# ReuseBlock_MSDriver2_0_2025-01-31.net
KiCad netlist of a schematic drawn in EasyEDA Pro
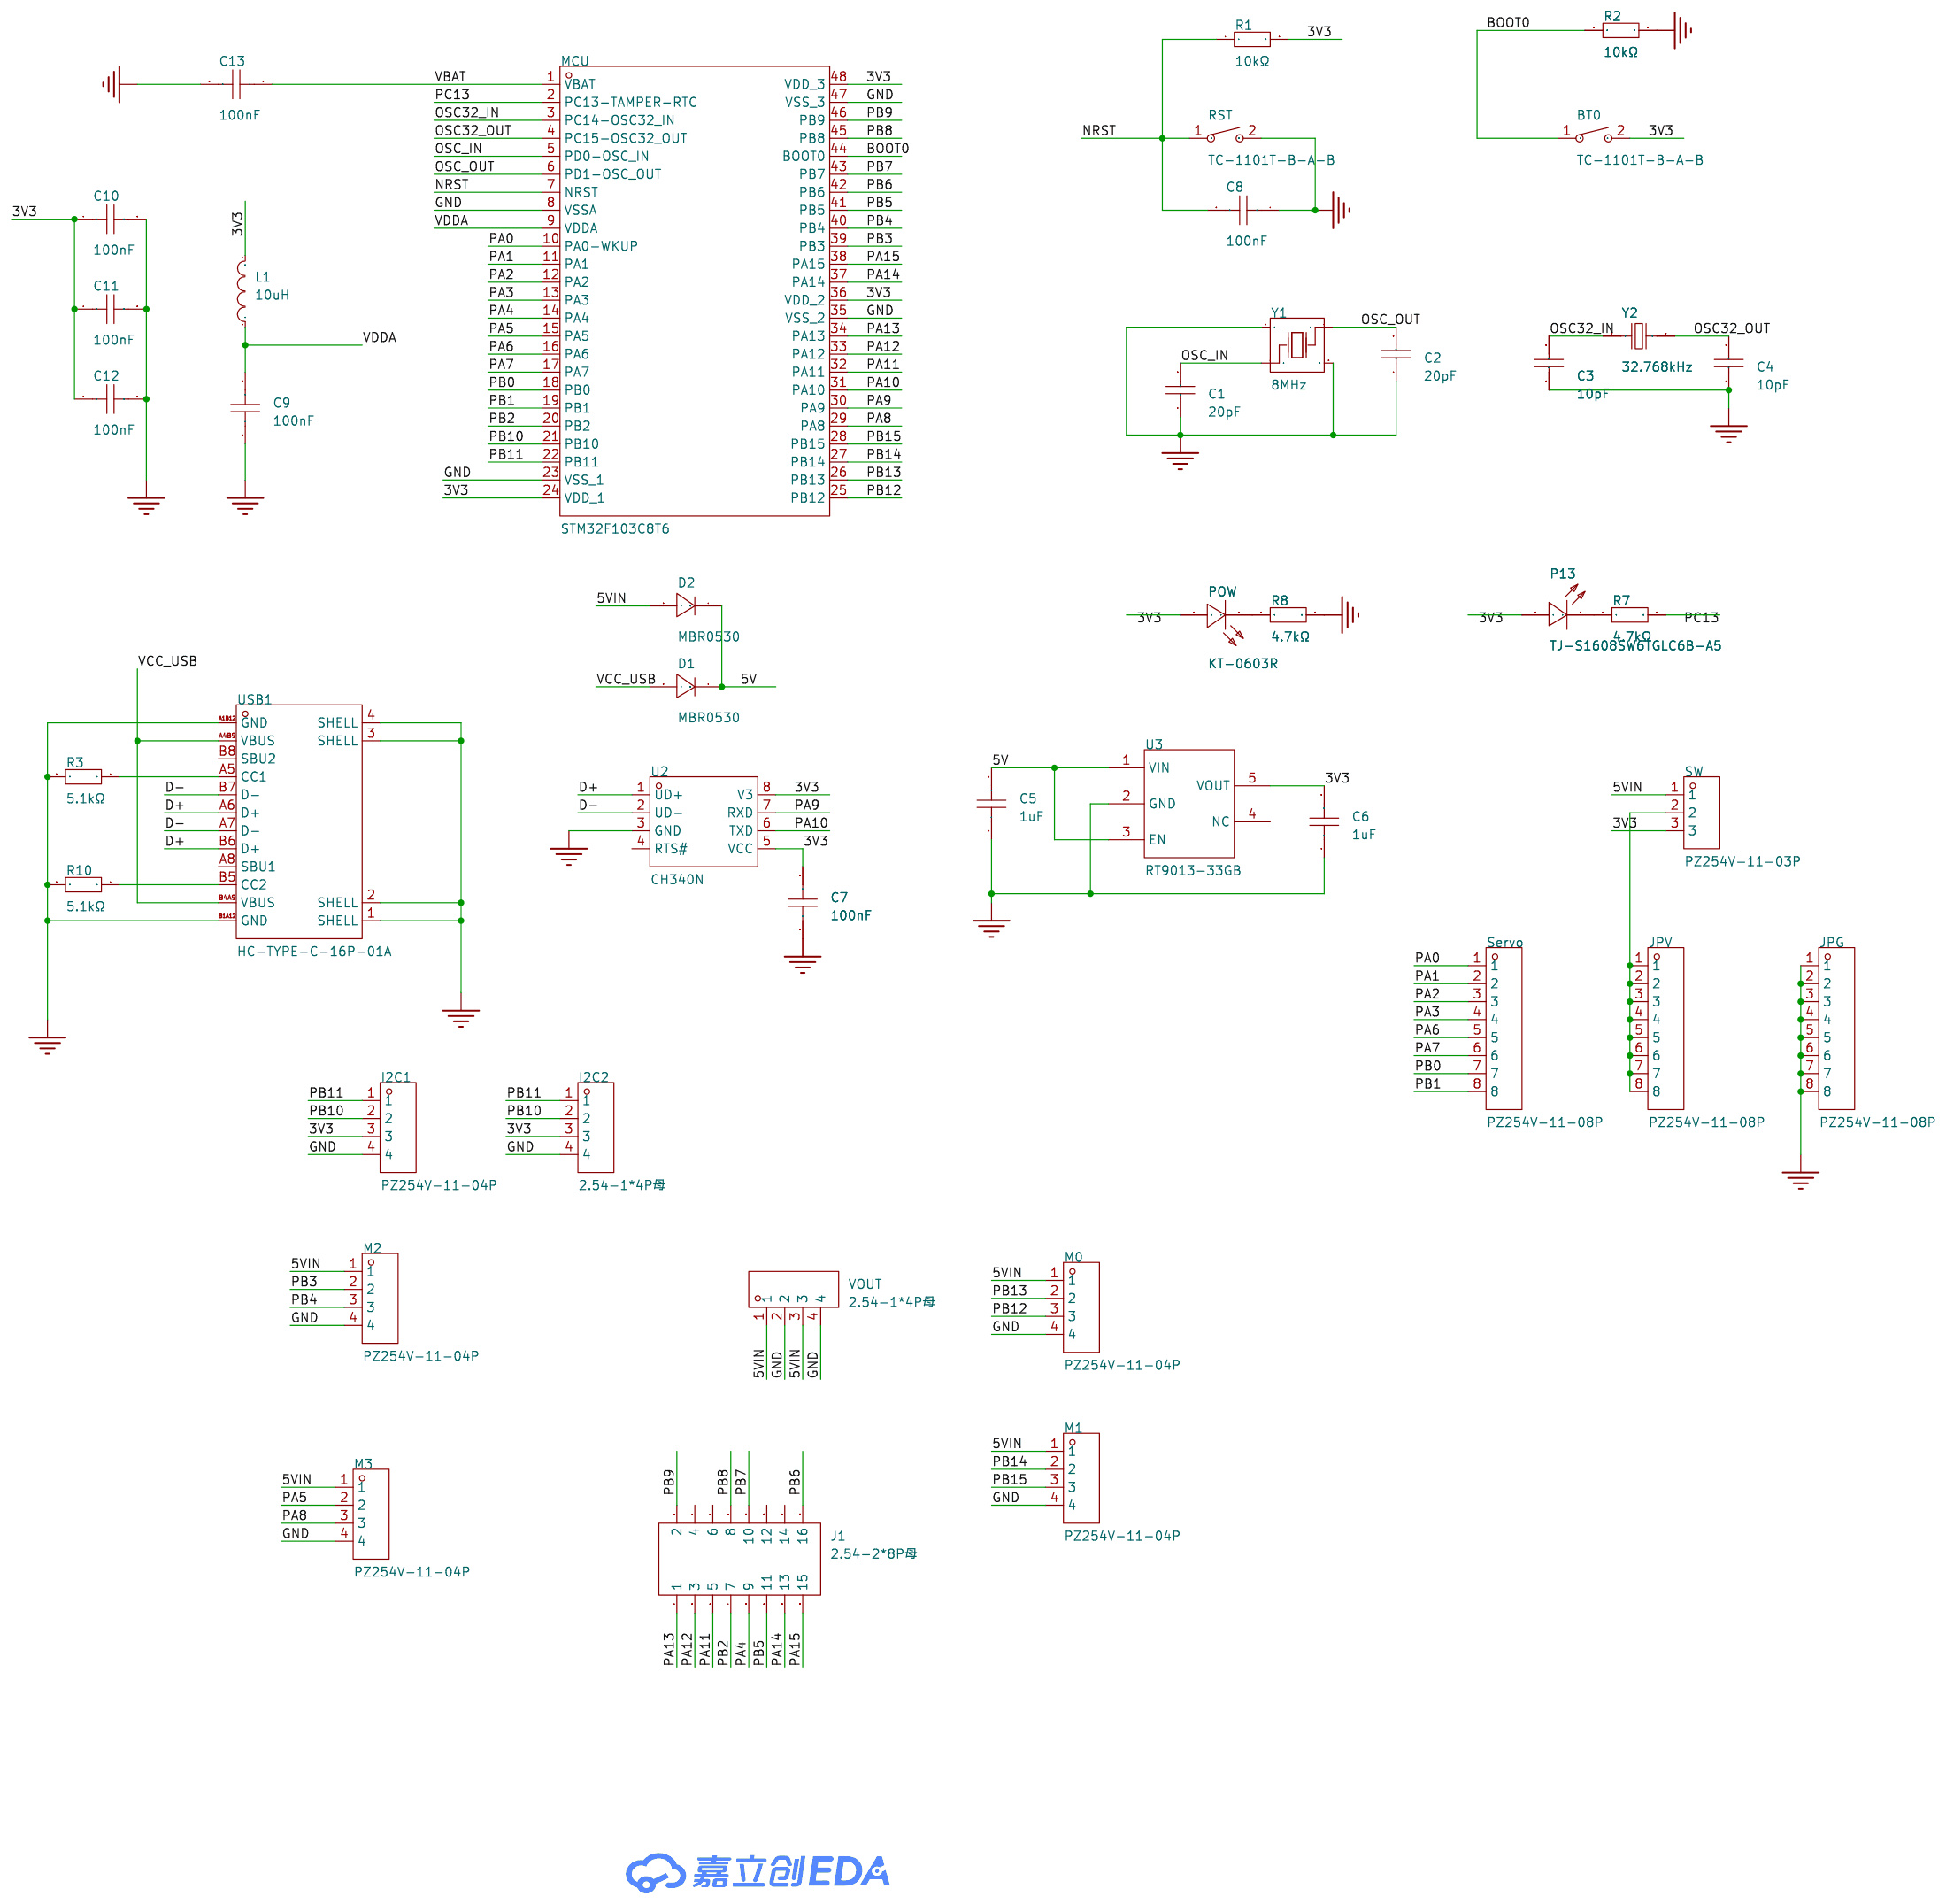
[diagram p0: schematic sheet]

(export (version "E")
  (design (tool "Eeschema 10.0.6"))
  (components
    (comp (ref "BT0")
      (value "TC-1101T-B-A-B")
      (footprint "easyedapro:KEY-TH_2P-L6.0-W3.5-P6.50")
      (fields (field (name "Manufacturer") "XKB Connectivity(中国星坤)"))
      (libsource (lib "easyedapro") (part "TC-1101T-B-A-B"))
    )
    (comp (ref "C1")
      (value "20pF")
      (footprint "easyedapro:C0603")
      (description "容值:20pF;精度:±5%;额定电压:50V;材质(温度系数):C0G;")
      (fields
        (field (name "Manufacturer Part") "CL10C200JB8NNNC")
        (field (name "Manufacturer") "SAMSUNG(三星)")
      )
      (libsource (lib "easyedapro") (part "CL10C200JB8NNNC"))
    )
    (comp (ref "C2")
      (value "20pF")
      (footprint "easyedapro:C0603")
      (description "容值:20pF;精度:±5%;额定电压:50V;材质(温度系数):C0G;")
      (fields
        (field (name "Manufacturer Part") "CL10C200JB8NNNC")
        (field (name "Manufacturer") "SAMSUNG(三星)")
      )
      (libsource (lib "easyedapro") (part "CL10C200JB8NNNC"))
    )
    (comp (ref "C3")
      (value "10pF")
      (footprint "easyedapro:C0603")
      (description "容值:10pF;精度:±5%;额定电压:50V;材质(温度系数):C0G;")
      (fields
        (field (name "Manufacturer Part") "CL10C100JB8NNNC")
        (field (name "Manufacturer") "SAMSUNG(三星)")
      )
      (libsource (lib "easyedapro") (part "CL10C100JB8NNNC"))
    )
    (comp (ref "C4")
      (value "10pF")
      (footprint "easyedapro:C0603")
      (description "容值:10pF;精度:±5%;额定电压:50V;材质(温度系数):C0G;")
      (fields
        (field (name "Manufacturer Part") "CL10C100JB8NNNC")
        (field (name "Manufacturer") "SAMSUNG(三星)")
      )
      (libsource (lib "easyedapro") (part "CL10C100JB8NNNC"))
    )
    (comp (ref "C5")
      (value "1uF")
      (footprint "easyedapro:C0603")
      (description "容值:1uF;精度:±10%;额定电压:50V;材质(温度系数):X5R;")
      (fields
        (field (name "Manufacturer Part") "CL10A105KB8NNNC")
        (field (name "Manufacturer") "SAMSUNG(三星)")
      )
      (libsource (lib "easyedapro") (part "CL10A105KB8NNNC"))
    )
    (comp (ref "C6")
      (value "1uF")
      (footprint "easyedapro:C0603")
      (description "容值:1uF;精度:±10%;额定电压:50V;材质(温度系数):X5R;")
      (fields
        (field (name "Manufacturer Part") "CL10A105KB8NNNC")
        (field (name "Manufacturer") "SAMSUNG(三星)")
      )
      (libsource (lib "easyedapro") (part "CL10A105KB8NNNC"))
    )
    (comp (ref "C7")
      (value "100nF")
      (footprint "easyedapro:C0603")
      (description "容值:100nF;精度:±10%;额定电压:50V;材质(温度系数):X7R;")
      (fields
        (field (name "Manufacturer Part") "CGA0603X7R104K500JT")
        (field (name "Manufacturer") "HRE(芯声)")
      )
      (libsource (lib "easyedapro") (part "CGA0603X7R104K500JT"))
    )
    (comp (ref "C8")
      (value "100nF")
      (footprint "easyedapro:C0603")
      (description "容值:100nF;精度:±10%;额定电压:50V;材质(温度系数):X7R;")
      (fields
        (field (name "Manufacturer Part") "CGA0603X7R104K500JT")
        (field (name "Manufacturer") "HRE(芯声)")
      )
      (libsource (lib "easyedapro") (part "CGA0603X7R104K500JT"))
    )
    (comp (ref "C9")
      (value "100nF")
      (footprint "easyedapro:C0603")
      (description "容值:100nF;精度:±10%;额定电压:50V;材质(温度系数):X7R;")
      (fields
        (field (name "Manufacturer Part") "CGA0603X7R104K500JT")
        (field (name "Manufacturer") "HRE(芯声)")
      )
      (libsource (lib "easyedapro") (part "CGA0603X7R104K500JT"))
    )
    (comp (ref "C10")
      (value "100nF")
      (footprint "easyedapro:C0603")
      (description "容值:100nF;精度:±10%;额定电压:50V;材质(温度系数):X7R;")
      (fields
        (field (name "Manufacturer Part") "CGA0603X7R104K500JT")
        (field (name "Manufacturer") "HRE(芯声)")
      )
      (libsource (lib "easyedapro") (part "CGA0603X7R104K500JT"))
    )
    (comp (ref "C11")
      (value "100nF")
      (footprint "easyedapro:C0603")
      (description "容值:100nF;精度:±10%;额定电压:50V;材质(温度系数):X7R;")
      (fields
        (field (name "Manufacturer Part") "CGA0603X7R104K500JT")
        (field (name "Manufacturer") "HRE(芯声)")
      )
      (libsource (lib "easyedapro") (part "CGA0603X7R104K500JT"))
    )
    (comp (ref "C12")
      (value "100nF")
      (footprint "easyedapro:C0603")
      (description "容值:100nF;精度:±10%;额定电压:50V;材质(温度系数):X7R;")
      (fields
        (field (name "Manufacturer Part") "CGA0603X7R104K500JT")
        (field (name "Manufacturer") "HRE(芯声)")
      )
      (libsource (lib "easyedapro") (part "CGA0603X7R104K500JT"))
    )
    (comp (ref "C13")
      (value "100nF")
      (footprint "easyedapro:C0603")
      (description "容值:100nF;精度:±10%;额定电压:50V;材质(温度系数):X7R;")
      (fields
        (field (name "Manufacturer Part") "CGA0603X7R104K500JT")
        (field (name "Manufacturer") "HRE(芯声)")
      )
      (libsource (lib "easyedapro") (part "CGA0603X7R104K500JT"))
    )
    (comp (ref "D1")
      (value "MBR0530")
      (footprint "easyedapro:SOD-123_L2.8-W1.8-LS3.7-RD")
      (description "二极管配置:-;正向压降(Vf):550mV@500mA;直流反向耐压(Vr):30V;整流电流:500mA;")
      (fields (field (name "Manufacturer") "CJ(江苏长电/长晶)"))
      (libsource (lib "easyedapro") (part "MBR0530"))
    )
    (comp (ref "D2")
      (value "MBR0530")
      (footprint "easyedapro:SOD-123_L2.8-W1.8-LS3.7-RD")
      (description "二极管配置:-;正向压降(Vf):550mV@500mA;直流反向耐压(Vr):30V;整流电流:500mA;")
      (fields (field (name "Manufacturer") "CJ(江苏长电/长晶)"))
      (libsource (lib "easyedapro") (part "MBR0530"))
    )
    (comp (ref "I2C1")
      (value "PZ254V-11-04P")
      (footprint "easyedapro:HDR-TH_4P-P2.54-V-M")
      (fields (field (name "Manufacturer") "XFCN(兴飞)"))
      (libsource (lib "easyedapro") (part "PZ254V-11-04P_C2691448"))
    )
    (comp (ref "I2C2")
      (value "2.54-1*4P母")
      (footprint "easyedapro:HDR-TH_4P-P2.54-V-F")
      (fields (field (name "Manufacturer") "BOOMELE(博穆精密)"))
      (libsource (lib "easyedapro") (part "2.54-1*4P母"))
    )
    (comp (ref "J1")
      (value "2.54-2*8P母")
      (footprint "easyedapro:HDR-TH_16P-P2.54-V-F-R2-C8-S2.54")
      (description "插孔结构:2x8P;间距:2.54mm;行距:2.54mm;安装类型:直插;排数:双排;总孔位数:16P;塑高:-;触头材质:黄铜;触头镀层:-;")
      (fields (field (name "Manufacturer") "BOOMELE(博穆精密)"))
      (libsource (lib "easyedapro") (part "Header-Female-2.54_2x8"))
    )
    (comp (ref "JPG")
      (value "PZ254V-11-08P")
      (footprint "easyedapro:HDR-TH_8P-P2.54-V-M")
      (fields (field (name "Manufacturer") "XFCN(兴飞)"))
      (libsource (lib "easyedapro") (part "PZ254V-11-08P"))
    )
    (comp (ref "JPV")
      (value "PZ254V-11-08P")
      (footprint "easyedapro:HDR-TH_8P-P2.54-V-M")
      (fields (field (name "Manufacturer") "XFCN(兴飞)"))
      (libsource (lib "easyedapro") (part "PZ254V-11-08P"))
    )
    (comp (ref "L1")
      (value "10uH")
      (footprint "easyedapro:L0805")
      (description "电感值:10uH;精度:±10%;额定电流:15mA;饱和电流(Isat):-;直流电阻(DCR):1.15Ω;")
      (fields
        (field (name "Manufacturer Part") "SDFL2012S100KTF")
        (field (name "Manufacturer") "Sunlord(顺络)")
      )
      (libsource (lib "easyedapro") (part "SDFL2012S100KTF"))
    )
    (comp (ref "M0")
      (value "PZ254V-11-04P")
      (footprint "easyedapro:HDR-TH_4P-P2.54-V-M")
      (fields (field (name "Manufacturer") "XFCN(兴飞)"))
      (libsource (lib "easyedapro") (part "PZ254V-11-04P_C2691448"))
    )
    (comp (ref "M1")
      (value "PZ254V-11-04P")
      (footprint "easyedapro:HDR-TH_4P-P2.54-V-M")
      (fields (field (name "Manufacturer") "XFCN(兴飞)"))
      (libsource (lib "easyedapro") (part "PZ254V-11-04P_C2691448"))
    )
    (comp (ref "M2")
      (value "PZ254V-11-04P")
      (footprint "easyedapro:HDR-TH_4P-P2.54-V-M")
      (fields (field (name "Manufacturer") "XFCN(兴飞)"))
      (libsource (lib "easyedapro") (part "PZ254V-11-04P_C2691448"))
    )
    (comp (ref "M3")
      (value "PZ254V-11-04P")
      (footprint "easyedapro:HDR-TH_4P-P2.54-V-M")
      (fields (field (name "Manufacturer") "XFCN(兴飞)"))
      (libsource (lib "easyedapro") (part "PZ254V-11-04P_C2691448"))
    )
    (comp (ref "MCU")
      (value "STM32F103C8T6")
      (footprint "easyedapro:LQFP-48_L7.0-W7.0-P0.50-LS9.0-BL")
      (description "CPU内核:ARM-M3;CPU最大主频:72MHz;应用领域:-;")
      (fields (field (name "Manufacturer") "ST(意法半导体)"))
      (libsource (lib "easyedapro") (part "STM32F103C8T6"))
    )
    (comp (ref "P13")
      (value "TJ-S1608SW6TGLC6B-A5")
      (footprint "easyedapro:LED0603-R-RD_BLUE")
      (description "发光颜色:蓝色;功率:111mW;正向电流:20mA;主波长:460nm;二极管配置:-;透镜颜色:无色透明透镜;色温:-;发光角度:120°;载带方式:-;工作温度:-40°C~+80°C;")
      (fields (field (name "Manufacturer") "TOGIALED(统佳)"))
      (libsource (lib "easyedapro") (part "TJ-S1608SW6TGLC6B-A5"))
    )
    (comp (ref "POW")
      (value "KT-0603R")
      (footprint "easyedapro:LED0603-RD")
      (description "发光颜色:红色;功率:-;正向电流:-;主波长:-;二极管配置:-;透镜颜色:-;色温:-;发光角度:-;载带方式:-;工作温度:-40°C~+85°C;")
      (fields (field (name "Manufacturer") "KENTO"))
      (libsource (lib "easyedapro") (part "KT-0603R"))
    )
    (comp (ref "R1")
      (value "10kΩ")
      (fields
        (field (name "Manufacturer Part") "0603WAF1002T5E")
        (field (name "Manufacturer") "UNI-ROYAL(厚声)")
      )
      (libsource (lib "easyedapro") (part "电阻"))
    )
    (comp (ref "R2")
      (value "10kΩ")
      (fields
        (field (name "Manufacturer Part") "0603WAF1002T5E")
        (field (name "Manufacturer") "UNI-ROYAL(厚声)")
      )
      (libsource (lib "easyedapro") (part "电阻"))
    )
    (comp (ref "R3")
      (value "5.1kΩ")
      (fields
        (field (name "Manufacturer Part") "0603WAF5101T5E")
        (field (name "Manufacturer") "UNI-ROYAL(厚声)")
      )
      (libsource (lib "easyedapro") (part "电阻"))
    )
    (comp (ref "R7")
      (value "4.7kΩ")
      (fields
        (field (name "Manufacturer Part") "0603WAF4701T5E")
        (field (name "Manufacturer") "UNI-ROYAL(厚声)")
      )
      (libsource (lib "easyedapro") (part "电阻"))
    )
    (comp (ref "R8")
      (value "4.7kΩ")
      (fields
        (field (name "Manufacturer Part") "0603WAF4701T5E")
        (field (name "Manufacturer") "UNI-ROYAL(厚声)")
      )
      (libsource (lib "easyedapro") (part "电阻"))
    )
    (comp (ref "R10")
      (value "5.1kΩ")
      (fields
        (field (name "Manufacturer Part") "0603WAF5101T5E")
        (field (name "Manufacturer") "UNI-ROYAL(厚声)")
      )
      (libsource (lib "easyedapro") (part "电阻"))
    )
    (comp (ref "RST")
      (value "TC-1101T-B-A-B")
      (footprint "easyedapro:KEY-TH_2P-L6.0-W3.5-P6.50")
      (fields (field (name "Manufacturer") "XKB Connectivity(中国星坤)"))
      (libsource (lib "easyedapro") (part "TC-1101T-B-A-B"))
    )
    (comp (ref "Servo")
      (value "PZ254V-11-08P")
      (footprint "easyedapro:HDR-TH_8P-P2.54-V-M")
      (fields (field (name "Manufacturer") "XFCN(兴飞)"))
      (libsource (lib "easyedapro") (part "PZ254V-11-08P"))
    )
    (comp (ref "SW")
      (value "PZ254V-11-03P")
      (footprint "easyedapro:HDR-TH_3P-P2.54-V-M")
      (fields (field (name "Manufacturer") "XFCN(兴飞)"))
      (libsource (lib "easyedapro") (part "PZ254V-11-03P_C2937625"))
    )
    (comp (ref "U2")
      (value "CH340N")
      (footprint "easyedapro:SOP-8_L4.9-W3.9-P1.27-LS6.0-BL")
      (description "应用功能:USB转串口;接口协议:USB 2.0;通道数:1;数据速率:2Mbps;")
      (fields (field (name "Manufacturer") "WCH(南京沁恒)"))
      (libsource (lib "easyedapro") (part "CH340N_C2977777"))
    )
    (comp (ref "U3")
      (value "RT9013-33GB")
      (footprint "easyedapro:SOT-23-5_L3.0-W1.7-P0.95-LS2.8-BL")
      (description "输出类型:固定;最大输入电压:5.5V;输出电压:3.3V;输出电流:500mA;电源纹波抑制比(PSRR):50dB@(10kHz);输出极性:正极;")
      (fields (field (name "Manufacturer") "RICHTEK(立锜)"))
      (libsource (lib "easyedapro") (part "RT9013-33GB"))
    )
    (comp (ref "USB1")
      (value "HC-TYPE-C-16P-01A")
      (footprint "easyedapro:USB-C-SMD_HC-TYPE-C-16P-01A")
      (fields (field (name "Manufacturer") "HCTL(华灿天禄)"))
      (libsource (lib "easyedapro") (part "HC-TYPE-C-16P-01A"))
    )
    (comp (ref "VOUT")
      (value "2.54-1*4P母")
      (footprint "easyedapro:HDR-TH_4P-P2.54-V-F")
      (fields (field (name "Manufacturer") "BOOMELE(博穆精密)"))
      (libsource (lib "easyedapro") (part "2.54-1*4P母"))
    )
    (comp (ref "Y1")
      (value "8MHz")
      (footprint "easyedapro:CRYSTAL-SMD_4P-L3.2-W2.5-BL")
      (description "晶振类型:贴片晶振;频率:8MHz;常温频差:±10ppm;负载电容:10pF;频率稳定度(全温):±15ppm;")
      (fields (field (name "Manufacturer Part") "TAXM8M4RDBCCT2T") (field (name "Manufacturer") "YJX(雅晶鑫)"))
      (libsource (lib "easyedapro") (part "TAXM8M4RDBCCT2T"))
    )
    (comp (ref "Y2")
      (value "32.768kHz")
      (footprint "easyedapro:FC-135R_L3.2-W1.5")
      (description "晶振类型:贴片晶振;频率:32.768kHz;常温频差:±20ppm;负载电容:12.5pF;")
      (fields (field (name "Manufacturer Part") "Q13FC13500004") (field (name "Manufacturer") "EPSON(爱普生)"))
      (libsource (lib "easyedapro") (part "Q13FC1350000400"))
    )
  )
  (nets
    (net (code "1") (name "/3V3") (class "Default")
      (node (ref "BT0") (pin "2") (pinfunction "2_2") (pintype "unspecified"))
      (node (ref "C10") (pin "1") (pinfunction "1_1") (pintype "unspecified"))
      (node (ref "C11") (pin "1") (pinfunction "1_1") (pintype "unspecified"))
      (node (ref "C12") (pin "1") (pinfunction "1_1") (pintype "unspecified"))
      (node (ref "C6") (pin "2") (pinfunction "2_2") (pintype "unspecified"))
      (node (ref "C7") (pin "2") (pinfunction "2_2") (pintype "unspecified"))
      (node (ref "I2C1") (pin "3") (pinfunction "3_3") (pintype "unspecified"))
      (node (ref "I2C2") (pin "3") (pinfunction "3_3") (pintype "unspecified"))
      (node (ref "L1") (pin "2") (pinfunction "2_2") (pintype "unspecified"))
      (node (ref "MCU") (pin "24") (pinfunction "VDD_1_24") (pintype "unspecified"))
      (node (ref "MCU") (pin "36") (pinfunction "VDD_2_36") (pintype "unspecified"))
      (node (ref "MCU") (pin "48") (pinfunction "VDD_3_48") (pintype "unspecified"))
      (node (ref "P13") (pin "1") (pinfunction "A_1") (pintype "unspecified"))
      (node (ref "POW") (pin "2") (pinfunction "A_2") (pintype "unspecified"))
      (node (ref "R1") (pin "2") (pinfunction "2_2") (pintype "input"))
      (node (ref "SW") (pin "3") (pinfunction "3_3") (pintype "unspecified"))
      (node (ref "U2") (pin "5") (pinfunction "VCC_5") (pintype "unspecified"))
      (node (ref "U2") (pin "8") (pinfunction "V3_8") (pintype "unspecified"))
      (node (ref "U3") (pin "5") (pinfunction "VOUT_5") (pintype "unspecified"))
    )
    (net (code "2") (name "/5V") (class "Default")
      (node (ref "C5") (pin "2") (pinfunction "2_2") (pintype "unspecified"))
      (node (ref "D1") (pin "1") (pinfunction "C_1") (pintype "unspecified"))
      (node (ref "D2") (pin "1") (pinfunction "C_1") (pintype "unspecified"))
      (node (ref "U3") (pin "1") (pinfunction "VIN_1") (pintype "unspecified"))
      (node (ref "U3") (pin "3") (pinfunction "EN_3") (pintype "unspecified"))
    )
    (net (code "3") (name "/5VIN") (class "Default")
      (node (ref "D2") (pin "2") (pinfunction "A_2") (pintype "unspecified"))
      (node (ref "M0") (pin "1") (pinfunction "1_1") (pintype "unspecified"))
      (node (ref "M1") (pin "1") (pinfunction "1_1") (pintype "unspecified"))
      (node (ref "M2") (pin "1") (pinfunction "1_1") (pintype "unspecified"))
      (node (ref "M3") (pin "1") (pinfunction "1_1") (pintype "unspecified"))
      (node (ref "SW") (pin "1") (pinfunction "1_1") (pintype "unspecified"))
      (node (ref "VOUT") (pin "1") (pinfunction "1_1") (pintype "unspecified"))
      (node (ref "VOUT") (pin "3") (pinfunction "3_3") (pintype "unspecified"))
    )
    (net (code "4") (name "/BOOT0") (class "Default")
      (node (ref "BT0") (pin "1") (pinfunction "1_1") (pintype "unspecified"))
      (node (ref "MCU") (pin "44") (pinfunction "BOOT0_44") (pintype "unspecified"))
      (node (ref "R2") (pin "1") (pinfunction "1_1") (pintype "input"))
    )
    (net (code "5") (name "/D+") (class "Default")
      (node (ref "U2") (pin "1") (pinfunction "UD+_1") (pintype "unspecified"))
      (node (ref "USB1") (pin "A6") (pinfunction "D+_A6") (pintype "unspecified"))
      (node (ref "USB1") (pin "B6") (pinfunction "D+_B6") (pintype "unspecified"))
    )
    (net (code "6") (name "/D-") (class "Default")
      (node (ref "U2") (pin "2") (pinfunction "UD-_2") (pintype "unspecified"))
      (node (ref "USB1") (pin "A7") (pinfunction "D-_A7") (pintype "unspecified"))
      (node (ref "USB1") (pin "B7") (pinfunction "D-_B7") (pintype "unspecified"))
    )
    (net (code "7") (name "/NRST") (class "Default")
      (node (ref "C8") (pin "2") (pinfunction "2_2") (pintype "unspecified"))
      (node (ref "MCU") (pin "7") (pinfunction "NRST_7") (pintype "unspecified"))
      (node (ref "R1") (pin "1") (pinfunction "1_1") (pintype "input"))
      (node (ref "RST") (pin "1") (pinfunction "1_1") (pintype "unspecified"))
    )
    (net (code "8") (name "/OSC32_IN") (class "Default")
      (node (ref "C3") (pin "2") (pinfunction "2_2") (pintype "input"))
      (node (ref "MCU") (pin "3") (pinfunction "PC14-OSC32_IN_3") (pintype "unspecified"))
      (node (ref "Y2") (pin "1") (pinfunction "1_1") (pintype "unspecified"))
    )
    (net (code "9") (name "/OSC32_OUT") (class "Default")
      (node (ref "C4") (pin "2") (pinfunction "2_2") (pintype "input"))
      (node (ref "MCU") (pin "4") (pinfunction "PC15-OSC32_OUT_4") (pintype "unspecified"))
      (node (ref "Y2") (pin "2") (pinfunction "2_2") (pintype "unspecified"))
    )
    (net (code "10") (name "/OSC_IN") (class "Default")
      (node (ref "C1") (pin "2") (pinfunction "2_2") (pintype "input"))
      (node (ref "MCU") (pin "5") (pinfunction "PD0-OSC_IN_5") (pintype "unspecified"))
      (node (ref "Y1") (pin "1") (pinfunction "1_1") (pintype "input"))
    )
    (net (code "11") (name "/OSC_OUT") (class "Default")
      (node (ref "C2") (pin "2") (pinfunction "2_2") (pintype "input"))
      (node (ref "MCU") (pin "6") (pinfunction "PD1-OSC_OUT_6") (pintype "unspecified"))
      (node (ref "Y1") (pin "3") (pinfunction "3_3") (pintype "input"))
    )
    (net (code "12") (name "/PA0") (class "Default")
      (node (ref "MCU") (pin "10") (pinfunction "PA0-WKUP_10") (pintype "unspecified"))
      (node (ref "Servo") (pin "1") (pinfunction "1_1") (pintype "unspecified"))
    )
    (net (code "13") (name "/PA1") (class "Default")
      (node (ref "MCU") (pin "11") (pinfunction "PA1_11") (pintype "unspecified"))
      (node (ref "Servo") (pin "2") (pinfunction "2_2") (pintype "unspecified"))
    )
    (net (code "14") (name "/PA2") (class "Default")
      (node (ref "MCU") (pin "12") (pinfunction "PA2_12") (pintype "unspecified"))
      (node (ref "Servo") (pin "3") (pinfunction "3_3") (pintype "unspecified"))
    )
    (net (code "15") (name "/PA3") (class "Default")
      (node (ref "MCU") (pin "13") (pinfunction "PA3_13") (pintype "unspecified"))
      (node (ref "Servo") (pin "4") (pinfunction "4_4") (pintype "unspecified"))
    )
    (net (code "16") (name "/PA4") (class "Default")
      (node (ref "J1") (pin "9") (pinfunction "9_9") (pintype "input"))
      (node (ref "MCU") (pin "14") (pinfunction "PA4_14") (pintype "unspecified"))
    )
    (net (code "17") (name "/PA5") (class "Default")
      (node (ref "M3") (pin "2") (pinfunction "2_2") (pintype "unspecified"))
      (node (ref "MCU") (pin "15") (pinfunction "PA5_15") (pintype "unspecified"))
    )
    (net (code "18") (name "/PA6") (class "Default")
      (node (ref "MCU") (pin "16") (pinfunction "PA6_16") (pintype "unspecified"))
      (node (ref "Servo") (pin "5") (pinfunction "5_5") (pintype "unspecified"))
    )
    (net (code "19") (name "/PA7") (class "Default")
      (node (ref "MCU") (pin "17") (pinfunction "PA7_17") (pintype "unspecified"))
      (node (ref "Servo") (pin "6") (pinfunction "6_6") (pintype "unspecified"))
    )
    (net (code "20") (name "/PA8") (class "Default")
      (node (ref "M3") (pin "3") (pinfunction "3_3") (pintype "unspecified"))
      (node (ref "MCU") (pin "29") (pinfunction "PA8_29") (pintype "unspecified"))
    )
    (net (code "21") (name "/PA9") (class "Default")
      (node (ref "MCU") (pin "30") (pinfunction "PA9_30") (pintype "unspecified"))
      (node (ref "U2") (pin "7") (pinfunction "RXD_7") (pintype "unspecified"))
    )
    (net (code "22") (name "/PA10") (class "Default")
      (node (ref "MCU") (pin "31") (pinfunction "PA10_31") (pintype "unspecified"))
      (node (ref "U2") (pin "6") (pinfunction "TXD_6") (pintype "unspecified"))
    )
    (net (code "23") (name "/PA11") (class "Default")
      (node (ref "J1") (pin "5") (pinfunction "5_5") (pintype "input"))
      (node (ref "MCU") (pin "32") (pinfunction "PA11_32") (pintype "unspecified"))
    )
    (net (code "24") (name "/PA12") (class "Default")
      (node (ref "J1") (pin "3") (pinfunction "3_3") (pintype "input"))
      (node (ref "MCU") (pin "33") (pinfunction "PA12_33") (pintype "unspecified"))
    )
    (net (code "25") (name "/PA13") (class "Default")
      (node (ref "J1") (pin "1") (pinfunction "1_1") (pintype "input"))
      (node (ref "MCU") (pin "34") (pinfunction "PA13_34") (pintype "unspecified"))
    )
    (net (code "26") (name "/PA14") (class "Default")
      (node (ref "J1") (pin "13") (pinfunction "13_13") (pintype "input"))
      (node (ref "MCU") (pin "37") (pinfunction "PA14_37") (pintype "unspecified"))
    )
    (net (code "27") (name "/PA15") (class "Default")
      (node (ref "J1") (pin "15") (pinfunction "15_15") (pintype "input"))
      (node (ref "MCU") (pin "38") (pinfunction "PA15_38") (pintype "unspecified"))
    )
    (net (code "28") (name "/PB0") (class "Default")
      (node (ref "MCU") (pin "18") (pinfunction "PB0_18") (pintype "unspecified"))
      (node (ref "Servo") (pin "7") (pinfunction "7_7") (pintype "unspecified"))
    )
    (net (code "29") (name "/PB1") (class "Default")
      (node (ref "MCU") (pin "19") (pinfunction "PB1_19") (pintype "unspecified"))
      (node (ref "Servo") (pin "8") (pinfunction "8_8") (pintype "unspecified"))
    )
    (net (code "30") (name "/PB2") (class "Default")
      (node (ref "J1") (pin "7") (pinfunction "7_7") (pintype "input"))
      (node (ref "MCU") (pin "20") (pinfunction "PB2_20") (pintype "unspecified"))
    )
    (net (code "31") (name "/PB3") (class "Default")
      (node (ref "M2") (pin "2") (pinfunction "2_2") (pintype "unspecified"))
      (node (ref "MCU") (pin "39") (pinfunction "PB3_39") (pintype "unspecified"))
    )
    (net (code "32") (name "/PB4") (class "Default")
      (node (ref "M2") (pin "3") (pinfunction "3_3") (pintype "unspecified"))
      (node (ref "MCU") (pin "40") (pinfunction "PB4_40") (pintype "unspecified"))
    )
    (net (code "33") (name "/PB5") (class "Default")
      (node (ref "J1") (pin "11") (pinfunction "11_11") (pintype "input"))
      (node (ref "MCU") (pin "41") (pinfunction "PB5_41") (pintype "unspecified"))
    )
    (net (code "34") (name "/PB6") (class "Default")
      (node (ref "J1") (pin "16") (pinfunction "16_16") (pintype "input"))
      (node (ref "MCU") (pin "42") (pinfunction "PB6_42") (pintype "unspecified"))
    )
    (net (code "35") (name "/PB7") (class "Default")
      (node (ref "J1") (pin "10") (pinfunction "10_10") (pintype "input"))
      (node (ref "MCU") (pin "43") (pinfunction "PB7_43") (pintype "unspecified"))
    )
    (net (code "36") (name "/PB8") (class "Default")
      (node (ref "J1") (pin "8") (pinfunction "8_8") (pintype "input"))
      (node (ref "MCU") (pin "45") (pinfunction "PB8_45") (pintype "unspecified"))
    )
    (net (code "37") (name "/PB9") (class "Default")
      (node (ref "J1") (pin "2") (pinfunction "2_2") (pintype "input"))
      (node (ref "MCU") (pin "46") (pinfunction "PB9_46") (pintype "unspecified"))
    )
    (net (code "38") (name "/PB10") (class "Default")
      (node (ref "I2C1") (pin "2") (pinfunction "2_2") (pintype "unspecified"))
      (node (ref "I2C2") (pin "2") (pinfunction "2_2") (pintype "unspecified"))
      (node (ref "MCU") (pin "21") (pinfunction "PB10_21") (pintype "unspecified"))
    )
    (net (code "39") (name "/PB11") (class "Default")
      (node (ref "I2C1") (pin "1") (pinfunction "1_1") (pintype "unspecified"))
      (node (ref "I2C2") (pin "1") (pinfunction "1_1") (pintype "unspecified"))
      (node (ref "MCU") (pin "22") (pinfunction "PB11_22") (pintype "unspecified"))
    )
    (net (code "40") (name "/PB12") (class "Default")
      (node (ref "M0") (pin "3") (pinfunction "3_3") (pintype "unspecified"))
      (node (ref "MCU") (pin "25") (pinfunction "PB12_25") (pintype "unspecified"))
    )
    (net (code "41") (name "/PB13") (class "Default")
      (node (ref "M0") (pin "2") (pinfunction "2_2") (pintype "unspecified"))
      (node (ref "MCU") (pin "26") (pinfunction "PB13_26") (pintype "unspecified"))
    )
    (net (code "42") (name "/PB14") (class "Default")
      (node (ref "M1") (pin "2") (pinfunction "2_2") (pintype "unspecified"))
      (node (ref "MCU") (pin "27") (pinfunction "PB14_27") (pintype "unspecified"))
    )
    (net (code "43") (name "/PB15") (class "Default")
      (node (ref "M1") (pin "3") (pinfunction "3_3") (pintype "unspecified"))
      (node (ref "MCU") (pin "28") (pinfunction "PB15_28") (pintype "unspecified"))
    )
    (net (code "44") (name "/PC13") (class "Default")
      (node (ref "MCU") (pin "2") (pinfunction "PC13-TAMPER-RTC_2") (pintype "unspecified"))
      (node (ref "R7") (pin "2") (pinfunction "2_2") (pintype "input"))
    )
    (net (code "45") (name "/VBAT") (class "Default")
      (node (ref "C13") (pin "1") (pinfunction "1_1") (pintype "unspecified"))
      (node (ref "MCU") (pin "1") (pinfunction "VBAT_1") (pintype "unspecified"))
    )
    (net (code "46") (name "/VCC_USB") (class "Default")
      (node (ref "D1") (pin "2") (pinfunction "A_2") (pintype "unspecified"))
      (node (ref "USB1") (pin "A4B9") (pinfunction "VBUS_A4B9") (pintype "unspecified"))
      (node (ref "USB1") (pin "B4A9") (pinfunction "VBUS_B4A9") (pintype "unspecified"))
    )
    (net (code "47") (name "/VDDA") (class "Default")
      (node (ref "C9") (pin "2") (pinfunction "2_2") (pintype "unspecified"))
      (node (ref "L1") (pin "1") (pinfunction "1_1") (pintype "unspecified"))
      (node (ref "MCU") (pin "9") (pinfunction "VDDA_9") (pintype "unspecified"))
    )
    (net (code "48") (name "GND") (class "Default")
      (node (ref "C1") (pin "1") (pinfunction "1_1") (pintype "input"))
      (node (ref "C10") (pin "2") (pinfunction "2_2") (pintype "unspecified"))
      (node (ref "C11") (pin "2") (pinfunction "2_2") (pintype "unspecified"))
      (node (ref "C12") (pin "2") (pinfunction "2_2") (pintype "unspecified"))
      (node (ref "C13") (pin "2") (pinfunction "2_2") (pintype "unspecified"))
      (node (ref "C2") (pin "1") (pinfunction "1_1") (pintype "input"))
      (node (ref "C3") (pin "1") (pinfunction "1_1") (pintype "input"))
      (node (ref "C4") (pin "1") (pinfunction "1_1") (pintype "input"))
      (node (ref "C5") (pin "1") (pinfunction "1_1") (pintype "unspecified"))
      (node (ref "C6") (pin "1") (pinfunction "1_1") (pintype "unspecified"))
      (node (ref "C7") (pin "1") (pinfunction "1_1") (pintype "unspecified"))
      (node (ref "C8") (pin "1") (pinfunction "1_1") (pintype "unspecified"))
      (node (ref "C9") (pin "1") (pinfunction "1_1") (pintype "unspecified"))
      (node (ref "I2C1") (pin "4") (pinfunction "4_4") (pintype "unspecified"))
      (node (ref "I2C2") (pin "4") (pinfunction "4_4") (pintype "unspecified"))
      (node (ref "JPG") (pin "1") (pinfunction "1_1") (pintype "unspecified"))
      (node (ref "JPG") (pin "2") (pinfunction "2_2") (pintype "unspecified"))
      (node (ref "JPG") (pin "3") (pinfunction "3_3") (pintype "unspecified"))
      (node (ref "JPG") (pin "4") (pinfunction "4_4") (pintype "unspecified"))
      (node (ref "JPG") (pin "5") (pinfunction "5_5") (pintype "unspecified"))
      (node (ref "JPG") (pin "6") (pinfunction "6_6") (pintype "unspecified"))
      (node (ref "JPG") (pin "7") (pinfunction "7_7") (pintype "unspecified"))
      (node (ref "JPG") (pin "8") (pinfunction "8_8") (pintype "unspecified"))
      (node (ref "M0") (pin "4") (pinfunction "4_4") (pintype "unspecified"))
      (node (ref "M1") (pin "4") (pinfunction "4_4") (pintype "unspecified"))
      (node (ref "M2") (pin "4") (pinfunction "4_4") (pintype "unspecified"))
      (node (ref "M3") (pin "4") (pinfunction "4_4") (pintype "unspecified"))
      (node (ref "MCU") (pin "23") (pinfunction "VSS_1_23") (pintype "unspecified"))
      (node (ref "MCU") (pin "35") (pinfunction "VSS_2_35") (pintype "unspecified"))
      (node (ref "MCU") (pin "47") (pinfunction "VSS_3_47") (pintype "unspecified"))
      (node (ref "MCU") (pin "8") (pinfunction "VSSA_8") (pintype "unspecified"))
      (node (ref "R10") (pin "2") (pinfunction "2_2") (pintype "input"))
      (node (ref "R2") (pin "2") (pinfunction "2_2") (pintype "input"))
      (node (ref "R3") (pin "2") (pinfunction "2_2") (pintype "input"))
      (node (ref "R8") (pin "2") (pinfunction "2_2") (pintype "input"))
      (node (ref "RST") (pin "2") (pinfunction "2_2") (pintype "unspecified"))
      (node (ref "U2") (pin "3") (pinfunction "GND_3") (pintype "unspecified"))
      (node (ref "U3") (pin "2") (pinfunction "GND_2") (pintype "unspecified"))
      (node (ref "USB1") (pin "1") (pinfunction "SHELL_1") (pintype "unspecified"))
      (node (ref "USB1") (pin "2") (pinfunction "SHELL_2") (pintype "unspecified"))
      (node (ref "USB1") (pin "3") (pinfunction "SHELL_3") (pintype "unspecified"))
      (node (ref "USB1") (pin "4") (pinfunction "SHELL_4") (pintype "unspecified"))
      (node (ref "USB1") (pin "A1B12") (pinfunction "GND_A1B12") (pintype "unspecified"))
      (node (ref "USB1") (pin "B1A12") (pinfunction "GND_B1A12") (pintype "unspecified"))
      (node (ref "VOUT") (pin "2") (pinfunction "2_2") (pintype "unspecified"))
      (node (ref "VOUT") (pin "4") (pinfunction "4_4") (pintype "unspecified"))
      (node (ref "Y1") (pin "2") (pinfunction "2_2") (pintype "input"))
      (node (ref "Y1") (pin "4") (pinfunction "4_4") (pintype "input"))
    )
    (net (code "49") (name "Net-(JPV-Pad1)") (class "Default")
      (node (ref "JPV") (pin "1") (pinfunction "1_1") (pintype "unspecified"))
      (node (ref "JPV") (pin "2") (pinfunction "2_2") (pintype "unspecified"))
      (node (ref "JPV") (pin "3") (pinfunction "3_3") (pintype "unspecified"))
      (node (ref "JPV") (pin "4") (pinfunction "4_4") (pintype "unspecified"))
      (node (ref "JPV") (pin "5") (pinfunction "5_5") (pintype "unspecified"))
      (node (ref "JPV") (pin "6") (pinfunction "6_6") (pintype "unspecified"))
      (node (ref "JPV") (pin "7") (pinfunction "7_7") (pintype "unspecified"))
      (node (ref "JPV") (pin "8") (pinfunction "8_8") (pintype "unspecified"))
      (node (ref "SW") (pin "2") (pinfunction "2_2") (pintype "unspecified"))
    )
    (net (code "50") (name "Net-(P13-K)") (class "Default")
      (node (ref "P13") (pin "2") (pinfunction "K_2") (pintype "unspecified"))
      (node (ref "R7") (pin "1") (pinfunction "1_1") (pintype "input"))
    )
    (net (code "51") (name "Net-(POW-K)") (class "Default")
      (node (ref "POW") (pin "1") (pinfunction "K_1") (pintype "unspecified"))
      (node (ref "R8") (pin "1") (pinfunction "1_1") (pintype "input"))
    )
    (net (code "52") (name "Net-(USB1-CC1)") (class "Default")
      (node (ref "R3") (pin "1") (pinfunction "1_1") (pintype "input"))
      (node (ref "USB1") (pin "A5") (pinfunction "CC1_A5") (pintype "unspecified"))
    )
    (net (code "53") (name "Net-(USB1-CC2)") (class "Default")
      (node (ref "R10") (pin "1") (pinfunction "1_1") (pintype "input"))
      (node (ref "USB1") (pin "B5") (pinfunction "CC2_B5") (pintype "unspecified"))
    )
    (net (code "54") (name "unconnected-(J1-Pad4)") (class "Default")
      (node (ref "J1") (pin "4") (pinfunction "4_4") (pintype "input"))
    )
    (net (code "55") (name "unconnected-(J1-Pad6)") (class "Default")
      (node (ref "J1") (pin "6") (pinfunction "6_6") (pintype "input"))
    )
    (net (code "56") (name "unconnected-(J1-Pad12)") (class "Default")
      (node (ref "J1") (pin "12") (pinfunction "12_12") (pintype "input"))
    )
    (net (code "57") (name "unconnected-(J1-Pad14)") (class "Default")
      (node (ref "J1") (pin "14") (pinfunction "14_14") (pintype "input"))
    )
    (net (code "58") (name "unconnected-(U2-RTS#-Pad4)") (class "Default")
      (node (ref "U2") (pin "4") (pinfunction "RTS#_4") (pintype "unspecified"))
    )
    (net (code "59") (name "unconnected-(U3-NC-Pad4)") (class "Default")
      (node (ref "U3") (pin "4") (pinfunction "NC_4") (pintype "unspecified"))
    )
    (net (code "60") (name "unconnected-(USB1-SBU1-PadA8)") (class "Default")
      (node (ref "USB1") (pin "A8") (pinfunction "SBU1_A8") (pintype "unspecified"))
    )
    (net (code "61") (name "unconnected-(USB1-SBU2-PadB8)") (class "Default")
      (node (ref "USB1") (pin "B8") (pinfunction "SBU2_B8") (pintype "unspecified"))
    )
  )
)
